# VALVEBOARD_ValvePower_ValveInterface.net
KiCad netlist of a schematic drawn in Altium Designer
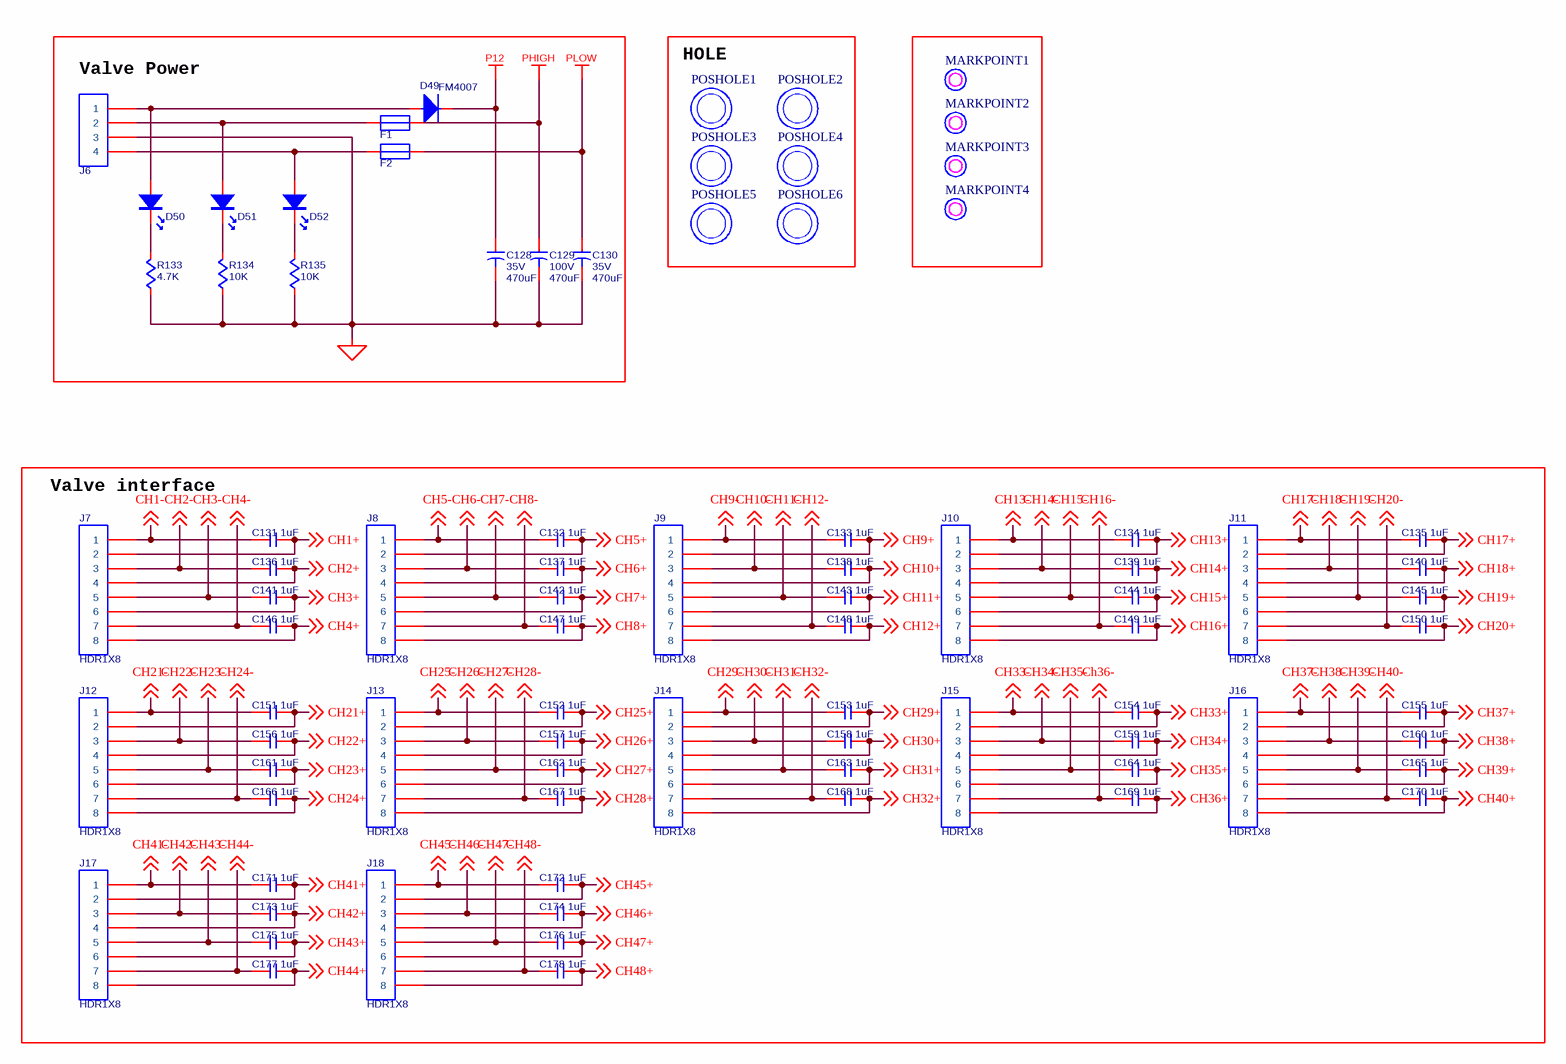
[diagram p0: VALVEBOARD_ValvePower_ValveInterface.SchDoc]

(export (version "E")
  (design (tool "Eeschema 10.0.6"))
  (components
    (comp (ref "C128")
      (value "470uF")
      (footprint "C_10_10R2")
      (fields (field (name "VOLTAGE") "35V") (field (name "Comment") "C-POL"))
      (libsource (lib "") (part "C-POL_1"))
    )
    (comp (ref "C129")
      (value "470uF")
      (footprint "C_18_21")
      (fields (field (name "VOLTAGE") "100V") (field (name "Comment") "C-POL"))
      (libsource (lib "zynq") (part "C-POL"))
    )
    (comp (ref "C130")
      (value "470uF")
      (footprint "C_10_10R2")
      (fields (field (name "VOLTAGE") "35V") (field (name "Comment") "C-POL"))
      (libsource (lib "") (part "C-POL_1"))
    )
    (comp (ref "C131")
      (value "1uF")
      (footprint "zynq:C0805")
      (fields (field (name "VOLTAGE") "25V") (field (name "Comment") "C-NOMO"))
      (libsource (lib "zynq") (part "C-NOMO"))
    )
    (comp (ref "C132")
      (value "1uF")
      (footprint "zynq:C0805")
      (fields (field (name "VOLTAGE") "25V") (field (name "Comment") "C-NOMO"))
      (libsource (lib "zynq") (part "C-NOMO"))
    )
    (comp (ref "C133")
      (value "1uF")
      (footprint "zynq:C0805")
      (fields (field (name "VOLTAGE") "25V") (field (name "Comment") "C-NOMO"))
      (libsource (lib "zynq") (part "C-NOMO"))
    )
    (comp (ref "C134")
      (value "1uF")
      (footprint "zynq:C0805")
      (fields (field (name "VOLTAGE") "25V") (field (name "Comment") "C-NOMO"))
      (libsource (lib "zynq") (part "C-NOMO"))
    )
    (comp (ref "C135")
      (value "1uF")
      (footprint "zynq:C0805")
      (fields (field (name "VOLTAGE") "25V") (field (name "Comment") "C-NOMO"))
      (libsource (lib "zynq") (part "C-NOMO"))
    )
    (comp (ref "C136")
      (value "1uF")
      (footprint "zynq:C0805")
      (fields (field (name "VOLTAGE") "25V") (field (name "Comment") "C-NOMO"))
      (libsource (lib "zynq") (part "C-NOMO"))
    )
    (comp (ref "C137")
      (value "1uF")
      (footprint "zynq:C0805")
      (fields (field (name "VOLTAGE") "25V") (field (name "Comment") "C-NOMO"))
      (libsource (lib "zynq") (part "C-NOMO"))
    )
    (comp (ref "C138")
      (value "1uF")
      (footprint "zynq:C0805")
      (fields (field (name "VOLTAGE") "25V") (field (name "Comment") "C-NOMO"))
      (libsource (lib "zynq") (part "C-NOMO"))
    )
    (comp (ref "C139")
      (value "1uF")
      (footprint "zynq:C0805")
      (fields (field (name "VOLTAGE") "25V") (field (name "Comment") "C-NOMO"))
      (libsource (lib "zynq") (part "C-NOMO"))
    )
    (comp (ref "C140")
      (value "1uF")
      (footprint "zynq:C0805")
      (fields (field (name "VOLTAGE") "25V") (field (name "Comment") "C-NOMO"))
      (libsource (lib "zynq") (part "C-NOMO"))
    )
    (comp (ref "C141")
      (value "1uF")
      (footprint "zynq:C0805")
      (fields (field (name "VOLTAGE") "25V") (field (name "Comment") "C-NOMO"))
      (libsource (lib "zynq") (part "C-NOMO"))
    )
    (comp (ref "C142")
      (value "1uF")
      (footprint "zynq:C0805")
      (fields (field (name "VOLTAGE") "25V") (field (name "Comment") "C-NOMO"))
      (libsource (lib "zynq") (part "C-NOMO"))
    )
    (comp (ref "C143")
      (value "1uF")
      (footprint "zynq:C0805")
      (fields (field (name "VOLTAGE") "25V") (field (name "Comment") "C-NOMO"))
      (libsource (lib "zynq") (part "C-NOMO"))
    )
    (comp (ref "C144")
      (value "1uF")
      (footprint "zynq:C0805")
      (fields (field (name "VOLTAGE") "25V") (field (name "Comment") "C-NOMO"))
      (libsource (lib "zynq") (part "C-NOMO"))
    )
    (comp (ref "C145")
      (value "1uF")
      (footprint "zynq:C0805")
      (fields (field (name "VOLTAGE") "25V") (field (name "Comment") "C-NOMO"))
      (libsource (lib "zynq") (part "C-NOMO"))
    )
    (comp (ref "C146")
      (value "1uF")
      (footprint "zynq:C0805")
      (fields (field (name "VOLTAGE") "25V") (field (name "Comment") "C-NOMO"))
      (libsource (lib "zynq") (part "C-NOMO"))
    )
    (comp (ref "C147")
      (value "1uF")
      (footprint "zynq:C0805")
      (fields (field (name "VOLTAGE") "25V") (field (name "Comment") "C-NOMO"))
      (libsource (lib "zynq") (part "C-NOMO"))
    )
    (comp (ref "C148")
      (value "1uF")
      (footprint "zynq:C0805")
      (fields (field (name "VOLTAGE") "25V") (field (name "Comment") "C-NOMO"))
      (libsource (lib "zynq") (part "C-NOMO"))
    )
    (comp (ref "C149")
      (value "1uF")
      (footprint "zynq:C0805")
      (fields (field (name "VOLTAGE") "25V") (field (name "Comment") "C-NOMO"))
      (libsource (lib "zynq") (part "C-NOMO"))
    )
    (comp (ref "C150")
      (value "1uF")
      (footprint "zynq:C0805")
      (fields (field (name "VOLTAGE") "25V") (field (name "Comment") "C-NOMO"))
      (libsource (lib "zynq") (part "C-NOMO"))
    )
    (comp (ref "C151")
      (value "1uF")
      (footprint "zynq:C0805")
      (fields (field (name "VOLTAGE") "25V") (field (name "Comment") "C-NOMO"))
      (libsource (lib "zynq") (part "C-NOMO"))
    )
    (comp (ref "C152")
      (value "1uF")
      (footprint "zynq:C0805")
      (fields (field (name "VOLTAGE") "25V") (field (name "Comment") "C-NOMO"))
      (libsource (lib "zynq") (part "C-NOMO"))
    )
    (comp (ref "C153")
      (value "1uF")
      (footprint "zynq:C0805")
      (fields (field (name "VOLTAGE") "25V") (field (name "Comment") "C-NOMO"))
      (libsource (lib "zynq") (part "C-NOMO"))
    )
    (comp (ref "C154")
      (value "1uF")
      (footprint "zynq:C0805")
      (fields (field (name "VOLTAGE") "25V") (field (name "Comment") "C-NOMO"))
      (libsource (lib "zynq") (part "C-NOMO"))
    )
    (comp (ref "C155")
      (value "1uF")
      (footprint "zynq:C0805")
      (fields (field (name "VOLTAGE") "25V") (field (name "Comment") "C-NOMO"))
      (libsource (lib "zynq") (part "C-NOMO"))
    )
    (comp (ref "C156")
      (value "1uF")
      (footprint "zynq:C0805")
      (fields (field (name "VOLTAGE") "25V") (field (name "Comment") "C-NOMO"))
      (libsource (lib "zynq") (part "C-NOMO"))
    )
    (comp (ref "C157")
      (value "1uF")
      (footprint "zynq:C0805")
      (fields (field (name "VOLTAGE") "25V") (field (name "Comment") "C-NOMO"))
      (libsource (lib "zynq") (part "C-NOMO"))
    )
    (comp (ref "C158")
      (value "1uF")
      (footprint "zynq:C0805")
      (fields (field (name "VOLTAGE") "25V") (field (name "Comment") "C-NOMO"))
      (libsource (lib "zynq") (part "C-NOMO"))
    )
    (comp (ref "C159")
      (value "1uF")
      (footprint "zynq:C0805")
      (fields (field (name "VOLTAGE") "25V") (field (name "Comment") "C-NOMO"))
      (libsource (lib "zynq") (part "C-NOMO"))
    )
    (comp (ref "C160")
      (value "1uF")
      (footprint "zynq:C0805")
      (fields (field (name "VOLTAGE") "25V") (field (name "Comment") "C-NOMO"))
      (libsource (lib "zynq") (part "C-NOMO"))
    )
    (comp (ref "C161")
      (value "1uF")
      (footprint "zynq:C0805")
      (fields (field (name "VOLTAGE") "25V") (field (name "Comment") "C-NOMO"))
      (libsource (lib "zynq") (part "C-NOMO"))
    )
    (comp (ref "C162")
      (value "1uF")
      (footprint "zynq:C0805")
      (fields (field (name "VOLTAGE") "25V") (field (name "Comment") "C-NOMO"))
      (libsource (lib "zynq") (part "C-NOMO"))
    )
    (comp (ref "C163")
      (value "1uF")
      (footprint "zynq:C0805")
      (fields (field (name "VOLTAGE") "25V") (field (name "Comment") "C-NOMO"))
      (libsource (lib "zynq") (part "C-NOMO"))
    )
    (comp (ref "C164")
      (value "1uF")
      (footprint "zynq:C0805")
      (fields (field (name "VOLTAGE") "25V") (field (name "Comment") "C-NOMO"))
      (libsource (lib "zynq") (part "C-NOMO"))
    )
    (comp (ref "C165")
      (value "1uF")
      (footprint "zynq:C0805")
      (fields (field (name "VOLTAGE") "25V") (field (name "Comment") "C-NOMO"))
      (libsource (lib "zynq") (part "C-NOMO"))
    )
    (comp (ref "C166")
      (value "1uF")
      (footprint "zynq:C0805")
      (fields (field (name "VOLTAGE") "25V") (field (name "Comment") "C-NOMO"))
      (libsource (lib "zynq") (part "C-NOMO"))
    )
    (comp (ref "C167")
      (value "1uF")
      (footprint "zynq:C0805")
      (fields (field (name "VOLTAGE") "25V") (field (name "Comment") "C-NOMO"))
      (libsource (lib "zynq") (part "C-NOMO"))
    )
    (comp (ref "C168")
      (value "1uF")
      (footprint "zynq:C0805")
      (fields (field (name "VOLTAGE") "25V") (field (name "Comment") "C-NOMO"))
      (libsource (lib "zynq") (part "C-NOMO"))
    )
    (comp (ref "C169")
      (value "1uF")
      (footprint "zynq:C0805")
      (fields (field (name "VOLTAGE") "25V") (field (name "Comment") "C-NOMO"))
      (libsource (lib "zynq") (part "C-NOMO"))
    )
    (comp (ref "C170")
      (value "1uF")
      (footprint "zynq:C0805")
      (fields (field (name "VOLTAGE") "25V") (field (name "Comment") "C-NOMO"))
      (libsource (lib "zynq") (part "C-NOMO"))
    )
    (comp (ref "C171")
      (value "1uF")
      (footprint "zynq:C0805")
      (fields (field (name "VOLTAGE") "25V") (field (name "Comment") "C-NOMO"))
      (libsource (lib "zynq") (part "C-NOMO"))
    )
    (comp (ref "C172")
      (value "1uF")
      (footprint "zynq:C0805")
      (fields (field (name "VOLTAGE") "25V") (field (name "Comment") "C-NOMO"))
      (libsource (lib "zynq") (part "C-NOMO"))
    )
    (comp (ref "C173")
      (value "1uF")
      (footprint "zynq:C0805")
      (fields (field (name "VOLTAGE") "25V") (field (name "Comment") "C-NOMO"))
      (libsource (lib "zynq") (part "C-NOMO"))
    )
    (comp (ref "C174")
      (value "1uF")
      (footprint "zynq:C0805")
      (fields (field (name "VOLTAGE") "25V") (field (name "Comment") "C-NOMO"))
      (libsource (lib "zynq") (part "C-NOMO"))
    )
    (comp (ref "C175")
      (value "1uF")
      (footprint "zynq:C0805")
      (fields (field (name "VOLTAGE") "25V") (field (name "Comment") "C-NOMO"))
      (libsource (lib "zynq") (part "C-NOMO"))
    )
    (comp (ref "C176")
      (value "1uF")
      (footprint "zynq:C0805")
      (fields (field (name "VOLTAGE") "25V") (field (name "Comment") "C-NOMO"))
      (libsource (lib "zynq") (part "C-NOMO"))
    )
    (comp (ref "C177")
      (value "1uF")
      (footprint "zynq:C0805")
      (fields (field (name "VOLTAGE") "25V") (field (name "Comment") "C-NOMO"))
      (libsource (lib "zynq") (part "C-NOMO"))
    )
    (comp (ref "C178")
      (value "1uF")
      (footprint "zynq:C0805")
      (fields (field (name "VOLTAGE") "25V") (field (name "Comment") "C-NOMO"))
      (libsource (lib "zynq") (part "C-NOMO"))
    )
    (comp (ref "D49")
      (value "FM4007")
      (footprint "zynq:FM4007-T(A7)")
      (libsource (lib "zynq") (part "FM4007"))
    )
    (comp (ref "D50") (value "LED") (footprint "zynq:LED0603") (libsource (lib "zynq") (part "LED")))
    (comp (ref "D51") (value "LED") (footprint "zynq:LED0603") (libsource (lib "zynq") (part "LED")))
    (comp (ref "D52") (value "LED") (footprint "zynq:LED0603") (libsource (lib "zynq") (part "LED")))
    (comp (ref "F1") (value "F50") (footprint "zynq:F-TH2") (libsource (lib "zynq") (part "F50")))
    (comp (ref "F2") (value "F50") (footprint "zynq:F-TH2") (libsource (lib "zynq") (part "F50")))
    (comp (ref "J6")
      (value "HDR1X4")
      (footprint "zynq:KF301-5.0-4P")
      (libsource (lib "zynq") (part "HDR1X4"))
    )
    (comp (ref "J7") (value "HDR1X8") (footprint "KF15EDGK-3.81-8P") (libsource (lib "zynq") (part "HDR1X8")))
    (comp (ref "J8") (value "HDR1X8") (footprint "KF15EDGK-3.81-8P") (libsource (lib "zynq") (part "HDR1X8")))
    (comp (ref "J9") (value "HDR1X8") (footprint "KF15EDGK-3.81-8P") (libsource (lib "zynq") (part "HDR1X8")))
    (comp (ref "J10")
      (value "HDR1X8")
      (footprint "KF15EDGK-3.81-8P")
      (libsource (lib "zynq") (part "HDR1X8"))
    )
    (comp (ref "J11")
      (value "HDR1X8")
      (footprint "KF15EDGK-3.81-8P")
      (libsource (lib "zynq") (part "HDR1X8"))
    )
    (comp (ref "J12")
      (value "HDR1X8")
      (footprint "KF15EDGK-3.81-8P")
      (libsource (lib "zynq") (part "HDR1X8"))
    )
    (comp (ref "J13")
      (value "HDR1X8")
      (footprint "KF15EDGK-3.81-8P")
      (libsource (lib "zynq") (part "HDR1X8"))
    )
    (comp (ref "J14")
      (value "HDR1X8")
      (footprint "KF15EDGK-3.81-8P")
      (libsource (lib "zynq") (part "HDR1X8"))
    )
    (comp (ref "J15")
      (value "HDR1X8")
      (footprint "KF15EDGK-3.81-8P")
      (libsource (lib "zynq") (part "HDR1X8"))
    )
    (comp (ref "J16")
      (value "HDR1X8")
      (footprint "KF15EDGK-3.81-8P")
      (libsource (lib "zynq") (part "HDR1X8"))
    )
    (comp (ref "J17")
      (value "HDR1X8")
      (footprint "KF15EDGK-3.81-8P")
      (libsource (lib "zynq") (part "HDR1X8"))
    )
    (comp (ref "J18")
      (value "HDR1X8")
      (footprint "KF15EDGK-3.81-8P")
      (libsource (lib "zynq") (part "HDR1X8"))
    )
    (comp (ref "MARKPOINT1")
      (value "MARKPOINT")
      (footprint "zynq:MARKPOINT-1.0")
      (libsource (lib "zynq") (part "MARKPOINT"))
    )
    (comp (ref "MARKPOINT2")
      (value "MARKPOINT")
      (footprint "zynq:MARKPOINT-1.0")
      (libsource (lib "zynq") (part "MARKPOINT"))
    )
    (comp (ref "MARKPOINT3")
      (value "MARKPOINT")
      (footprint "zynq:MARKPOINT-1.0")
      (libsource (lib "zynq") (part "MARKPOINT"))
    )
    (comp (ref "MARKPOINT4")
      (value "MARKPOINT")
      (footprint "zynq:MARKPOINT-1.0")
      (libsource (lib "zynq") (part "MARKPOINT"))
    )
    (comp (ref "POSHOLE1")
      (value "POSHOLE")
      (footprint "zynq:POSHOLE-3.2")
      (libsource (lib "zynq") (part "POSHOLE"))
    )
    (comp (ref "POSHOLE2")
      (value "POSHOLE")
      (footprint "zynq:POSHOLE-3.2")
      (libsource (lib "zynq") (part "POSHOLE"))
    )
    (comp (ref "POSHOLE3")
      (value "POSHOLE")
      (footprint "zynq:POSHOLE-3.2")
      (libsource (lib "zynq") (part "POSHOLE"))
    )
    (comp (ref "POSHOLE4")
      (value "POSHOLE")
      (footprint "zynq:POSHOLE-3.2")
      (libsource (lib "zynq") (part "POSHOLE"))
    )
    (comp (ref "POSHOLE5")
      (value "POSHOLE")
      (footprint "zynq:POSHOLE-3.2")
      (libsource (lib "zynq") (part "POSHOLE"))
    )
    (comp (ref "POSHOLE6")
      (value "POSHOLE")
      (footprint "zynq:POSHOLE-3.2")
      (libsource (lib "zynq") (part "POSHOLE"))
    )
    (comp (ref "R133")
      (value "4.7K")
      (footprint "zynq:R0402")
      (fields (field (name "Comment") "R"))
      (libsource (lib "zynq") (part "R"))
    )
    (comp (ref "R134")
      (value "10K")
      (footprint "zynq:R0402")
      (fields (field (name "Comment") "R"))
      (libsource (lib "zynq") (part "R"))
    )
    (comp (ref "R135")
      (value "10K")
      (footprint "zynq:R0402")
      (fields (field (name "Comment") "R"))
      (libsource (lib "zynq") (part "R"))
    )
  )
  (nets
    (net (code "2") (name "CH1+") (class "Default")
      (node (ref "C131") (pin "1") (pinfunction "1_1") (pintype "passive"))
      (node (ref "J7") (pin "2") (pinfunction "2_2") (pintype "passive"))
    )
    (net (code "3") (name "CH1-") (class "Default")
      (node (ref "C131") (pin "2") (pinfunction "2_2") (pintype "passive"))
      (node (ref "J7") (pin "1") (pinfunction "1_1") (pintype "passive"))
    )
    (net (code "4") (name "CH2+") (class "Default")
      (node (ref "C136") (pin "1") (pinfunction "1_1") (pintype "passive"))
      (node (ref "J7") (pin "4") (pinfunction "4_4") (pintype "passive"))
    )
    (net (code "5") (name "CH2-") (class "Default")
      (node (ref "C136") (pin "2") (pinfunction "2_2") (pintype "passive"))
      (node (ref "J7") (pin "3") (pinfunction "3_3") (pintype "passive"))
    )
    (net (code "6") (name "CH3+") (class "Default")
      (node (ref "C141") (pin "1") (pinfunction "1_1") (pintype "passive"))
      (node (ref "J7") (pin "6") (pinfunction "6_6") (pintype "passive"))
    )
    (net (code "7") (name "CH3-") (class "Default")
      (node (ref "C141") (pin "2") (pinfunction "2_2") (pintype "passive"))
      (node (ref "J7") (pin "5") (pinfunction "5_5") (pintype "passive"))
    )
    (net (code "8") (name "CH4+") (class "Default")
      (node (ref "C146") (pin "1") (pinfunction "1_1") (pintype "passive"))
      (node (ref "J7") (pin "8") (pinfunction "8_8") (pintype "passive"))
    )
    (net (code "9") (name "CH4-") (class "Default")
      (node (ref "C146") (pin "2") (pinfunction "2_2") (pintype "passive"))
      (node (ref "J7") (pin "7") (pinfunction "7_7") (pintype "passive"))
    )
    (net (code "10") (name "CH5+") (class "Default")
      (node (ref "C132") (pin "1") (pinfunction "1_1") (pintype "passive"))
      (node (ref "J8") (pin "2") (pinfunction "2_2") (pintype "passive"))
    )
    (net (code "11") (name "CH5-") (class "Default")
      (node (ref "C132") (pin "2") (pinfunction "2_2") (pintype "passive"))
      (node (ref "J8") (pin "1") (pinfunction "1_1") (pintype "passive"))
    )
    (net (code "12") (name "CH6+") (class "Default")
      (node (ref "C137") (pin "1") (pinfunction "1_1") (pintype "passive"))
      (node (ref "J8") (pin "4") (pinfunction "4_4") (pintype "passive"))
    )
    (net (code "13") (name "CH6-") (class "Default")
      (node (ref "C137") (pin "2") (pinfunction "2_2") (pintype "passive"))
      (node (ref "J8") (pin "3") (pinfunction "3_3") (pintype "passive"))
    )
    (net (code "14") (name "CH7+") (class "Default")
      (node (ref "C142") (pin "1") (pinfunction "1_1") (pintype "passive"))
      (node (ref "J8") (pin "6") (pinfunction "6_6") (pintype "passive"))
    )
    (net (code "15") (name "CH7-") (class "Default")
      (node (ref "C142") (pin "2") (pinfunction "2_2") (pintype "passive"))
      (node (ref "J8") (pin "5") (pinfunction "5_5") (pintype "passive"))
    )
    (net (code "16") (name "CH8+") (class "Default")
      (node (ref "C147") (pin "1") (pinfunction "1_1") (pintype "passive"))
      (node (ref "J8") (pin "8") (pinfunction "8_8") (pintype "passive"))
    )
    (net (code "17") (name "CH8-") (class "Default")
      (node (ref "C147") (pin "2") (pinfunction "2_2") (pintype "passive"))
      (node (ref "J8") (pin "7") (pinfunction "7_7") (pintype "passive"))
    )
    (net (code "18") (name "CH9+") (class "Default")
      (node (ref "C133") (pin "1") (pinfunction "1_1") (pintype "passive"))
      (node (ref "J9") (pin "2") (pinfunction "2_2") (pintype "passive"))
    )
    (net (code "19") (name "CH9-") (class "Default")
      (node (ref "C133") (pin "2") (pinfunction "2_2") (pintype "passive"))
      (node (ref "J9") (pin "1") (pinfunction "1_1") (pintype "passive"))
    )
    (net (code "20") (name "CH10+") (class "Default")
      (node (ref "C138") (pin "1") (pinfunction "1_1") (pintype "passive"))
      (node (ref "J9") (pin "4") (pinfunction "4_4") (pintype "passive"))
    )
    (net (code "21") (name "CH10-") (class "Default")
      (node (ref "C138") (pin "2") (pinfunction "2_2") (pintype "passive"))
      (node (ref "J9") (pin "3") (pinfunction "3_3") (pintype "passive"))
    )
    (net (code "22") (name "CH11+") (class "Default")
      (node (ref "C143") (pin "1") (pinfunction "1_1") (pintype "passive"))
      (node (ref "J9") (pin "6") (pinfunction "6_6") (pintype "passive"))
    )
    (net (code "23") (name "CH11-") (class "Default")
      (node (ref "C143") (pin "2") (pinfunction "2_2") (pintype "passive"))
      (node (ref "J9") (pin "5") (pinfunction "5_5") (pintype "passive"))
    )
    (net (code "24") (name "CH12+") (class "Default")
      (node (ref "C148") (pin "1") (pinfunction "1_1") (pintype "passive"))
      (node (ref "J9") (pin "8") (pinfunction "8_8") (pintype "passive"))
    )
    (net (code "25") (name "CH12-") (class "Default")
      (node (ref "C148") (pin "2") (pinfunction "2_2") (pintype "passive"))
      (node (ref "J9") (pin "7") (pinfunction "7_7") (pintype "passive"))
    )
    (net (code "26") (name "CH13+") (class "Default")
      (node (ref "C134") (pin "1") (pinfunction "1_1") (pintype "passive"))
      (node (ref "J10") (pin "2") (pinfunction "2_2") (pintype "passive"))
    )
    (net (code "27") (name "CH13-") (class "Default")
      (node (ref "C134") (pin "2") (pinfunction "2_2") (pintype "passive"))
      (node (ref "J10") (pin "1") (pinfunction "1_1") (pintype "passive"))
    )
    (net (code "28") (name "CH14+") (class "Default")
      (node (ref "C139") (pin "1") (pinfunction "1_1") (pintype "passive"))
      (node (ref "J10") (pin "4") (pinfunction "4_4") (pintype "passive"))
    )
    (net (code "29") (name "CH14-") (class "Default")
      (node (ref "C139") (pin "2") (pinfunction "2_2") (pintype "passive"))
      (node (ref "J10") (pin "3") (pinfunction "3_3") (pintype "passive"))
    )
    (net (code "30") (name "CH15+") (class "Default")
      (node (ref "C144") (pin "1") (pinfunction "1_1") (pintype "passive"))
      (node (ref "J10") (pin "6") (pinfunction "6_6") (pintype "passive"))
    )
    (net (code "31") (name "CH15-") (class "Default")
      (node (ref "C144") (pin "2") (pinfunction "2_2") (pintype "passive"))
      (node (ref "J10") (pin "5") (pinfunction "5_5") (pintype "passive"))
    )
    (net (code "32") (name "CH16+") (class "Default")
      (node (ref "C149") (pin "1") (pinfunction "1_1") (pintype "passive"))
      (node (ref "J10") (pin "8") (pinfunction "8_8") (pintype "passive"))
    )
    (net (code "33") (name "CH16-") (class "Default")
      (node (ref "C149") (pin "2") (pinfunction "2_2") (pintype "passive"))
      (node (ref "J10") (pin "7") (pinfunction "7_7") (pintype "passive"))
    )
    (net (code "34") (name "CH17+") (class "Default")
      (node (ref "C135") (pin "1") (pinfunction "1_1") (pintype "passive"))
      (node (ref "J11") (pin "2") (pinfunction "2_2") (pintype "passive"))
    )
    (net (code "35") (name "CH17-") (class "Default")
      (node (ref "C135") (pin "2") (pinfunction "2_2") (pintype "passive"))
      (node (ref "J11") (pin "1") (pinfunction "1_1") (pintype "passive"))
    )
    (net (code "36") (name "CH18+") (class "Default")
      (node (ref "C140") (pin "1") (pinfunction "1_1") (pintype "passive"))
      (node (ref "J11") (pin "4") (pinfunction "4_4") (pintype "passive"))
    )
    (net (code "37") (name "CH18-") (class "Default")
      (node (ref "C140") (pin "2") (pinfunction "2_2") (pintype "passive"))
      (node (ref "J11") (pin "3") (pinfunction "3_3") (pintype "passive"))
    )
    (net (code "38") (name "CH19+") (class "Default")
      (node (ref "C145") (pin "1") (pinfunction "1_1") (pintype "passive"))
      (node (ref "J11") (pin "6") (pinfunction "6_6") (pintype "passive"))
    )
    (net (code "39") (name "CH19-") (class "Default")
      (node (ref "C145") (pin "2") (pinfunction "2_2") (pintype "passive"))
      (node (ref "J11") (pin "5") (pinfunction "5_5") (pintype "passive"))
    )
    (net (code "40") (name "CH20+") (class "Default")
      (node (ref "C150") (pin "1") (pinfunction "1_1") (pintype "passive"))
      (node (ref "J11") (pin "8") (pinfunction "8_8") (pintype "passive"))
    )
    (net (code "41") (name "CH20-") (class "Default")
      (node (ref "C150") (pin "2") (pinfunction "2_2") (pintype "passive"))
      (node (ref "J11") (pin "7") (pinfunction "7_7") (pintype "passive"))
    )
    (net (code "42") (name "CH21+") (class "Default")
      (node (ref "C151") (pin "1") (pinfunction "1_1") (pintype "passive"))
      (node (ref "J12") (pin "2") (pinfunction "2_2") (pintype "passive"))
    )
    (net (code "43") (name "CH21-") (class "Default")
      (node (ref "C151") (pin "2") (pinfunction "2_2") (pintype "passive"))
      (node (ref "J12") (pin "1") (pinfunction "1_1") (pintype "passive"))
    )
    (net (code "44") (name "CH22+") (class "Default")
      (node (ref "C156") (pin "1") (pinfunction "1_1") (pintype "passive"))
      (node (ref "J12") (pin "4") (pinfunction "4_4") (pintype "passive"))
    )
    (net (code "45") (name "CH22-") (class "Default")
      (node (ref "C156") (pin "2") (pinfunction "2_2") (pintype "passive"))
      (node (ref "J12") (pin "3") (pinfunction "3_3") (pintype "passive"))
    )
    (net (code "46") (name "CH23+") (class "Default")
      (node (ref "C161") (pin "1") (pinfunction "1_1") (pintype "passive"))
      (node (ref "J12") (pin "6") (pinfunction "6_6") (pintype "passive"))
    )
    (net (code "47") (name "CH23-") (class "Default")
      (node (ref "C161") (pin "2") (pinfunction "2_2") (pintype "passive"))
      (node (ref "J12") (pin "5") (pinfunction "5_5") (pintype "passive"))
    )
    (net (code "48") (name "CH24+") (class "Default")
      (node (ref "C166") (pin "1") (pinfunction "1_1") (pintype "passive"))
      (node (ref "J12") (pin "8") (pinfunction "8_8") (pintype "passive"))
    )
    (net (code "49") (name "CH24-") (class "Default")
      (node (ref "C166") (pin "2") (pinfunction "2_2") (pintype "passive"))
      (node (ref "J12") (pin "7") (pinfunction "7_7") (pintype "passive"))
    )
    (net (code "50") (name "CH25+") (class "Default")
      (node (ref "C152") (pin "1") (pinfunction "1_1") (pintype "passive"))
      (node (ref "J13") (pin "2") (pinfunction "2_2") (pintype "passive"))
    )
    (net (code "51") (name "CH25-") (class "Default")
      (node (ref "C152") (pin "2") (pinfunction "2_2") (pintype "passive"))
      (node (ref "J13") (pin "1") (pinfunction "1_1") (pintype "passive"))
    )
    (net (code "52") (name "CH26+") (class "Default")
      (node (ref "C157") (pin "1") (pinfunction "1_1") (pintype "passive"))
      (node (ref "J13") (pin "4") (pinfunction "4_4") (pintype "passive"))
    )
    (net (code "53") (name "CH26-") (class "Default")
      (node (ref "C157") (pin "2") (pinfunction "2_2") (pintype "passive"))
      (node (ref "J13") (pin "3") (pinfunction "3_3") (pintype "passive"))
    )
    (net (code "54") (name "CH27+") (class "Default")
      (node (ref "C162") (pin "1") (pinfunction "1_1") (pintype "passive"))
      (node (ref "J13") (pin "6") (pinfunction "6_6") (pintype "passive"))
    )
    (net (code "55") (name "CH27-") (class "Default")
      (node (ref "C162") (pin "2") (pinfunction "2_2") (pintype "passive"))
      (node (ref "J13") (pin "5") (pinfunction "5_5") (pintype "passive"))
    )
    (net (code "56") (name "CH28+") (class "Default")
      (node (ref "C167") (pin "1") (pinfunction "1_1") (pintype "passive"))
      (node (ref "J13") (pin "8") (pinfunction "8_8") (pintype "passive"))
    )
    (net (code "57") (name "CH28-") (class "Default")
      (node (ref "C167") (pin "2") (pinfunction "2_2") (pintype "passive"))
      (node (ref "J13") (pin "7") (pinfunction "7_7") (pintype "passive"))
    )
    (net (code "58") (name "CH29+") (class "Default")
      (node (ref "C153") (pin "1") (pinfunction "1_1") (pintype "passive"))
      (node (ref "J14") (pin "2") (pinfunction "2_2") (pintype "passive"))
    )
    (net (code "59") (name "CH29-") (class "Default")
      (node (ref "C153") (pin "2") (pinfunction "2_2") (pintype "passive"))
      (node (ref "J14") (pin "1") (pinfunction "1_1") (pintype "passive"))
    )
    (net (code "60") (name "CH30+") (class "Default")
      (node (ref "C158") (pin "1") (pinfunction "1_1") (pintype "passive"))
      (node (ref "J14") (pin "4") (pinfunction "4_4") (pintype "passive"))
    )
    (net (code "61") (name "CH30-") (class "Default")
      (node (ref "C158") (pin "2") (pinfunction "2_2") (pintype "passive"))
      (node (ref "J14") (pin "3") (pinfunction "3_3") (pintype "passive"))
    )
    (net (code "62") (name "CH31+") (class "Default")
      (node (ref "C163") (pin "1") (pinfunction "1_1") (pintype "passive"))
      (node (ref "J14") (pin "6") (pinfunction "6_6") (pintype "passive"))
    )
    (net (code "63") (name "CH31-") (class "Default")
      (node (ref "C163") (pin "2") (pinfunction "2_2") (pintype "passive"))
      (node (ref "J14") (pin "5") (pinfunction "5_5") (pintype "passive"))
    )
    (net (code "64") (name "CH32+") (class "Default")
      (node (ref "C168") (pin "1") (pinfunction "1_1") (pintype "passive"))
      (node (ref "J14") (pin "8") (pinfunction "8_8") (pintype "passive"))
    )
    (net (code "65") (name "CH32-") (class "Default")
      (node (ref "C168") (pin "2") (pinfunction "2_2") (pintype "passive"))
      (node (ref "J14") (pin "7") (pinfunction "7_7") (pintype "passive"))
    )
    (net (code "66") (name "CH33+") (class "Default")
      (node (ref "C154") (pin "1") (pinfunction "1_1") (pintype "passive"))
      (node (ref "J15") (pin "2") (pinfunction "2_2") (pintype "passive"))
    )
    (net (code "67") (name "CH33-") (class "Default")
      (node (ref "C154") (pin "2") (pinfunction "2_2") (pintype "passive"))
      (node (ref "J15") (pin "1") (pinfunction "1_1") (pintype "passive"))
    )
    (net (code "68") (name "CH34+") (class "Default")
      (node (ref "C159") (pin "1") (pinfunction "1_1") (pintype "passive"))
      (node (ref "J15") (pin "4") (pinfunction "4_4") (pintype "passive"))
    )
    (net (code "69") (name "CH34-") (class "Default")
      (node (ref "C159") (pin "2") (pinfunction "2_2") (pintype "passive"))
      (node (ref "J15") (pin "3") (pinfunction "3_3") (pintype "passive"))
    )
    (net (code "70") (name "CH35+") (class "Default")
      (node (ref "C164") (pin "1") (pinfunction "1_1") (pintype "passive"))
      (node (ref "J15") (pin "6") (pinfunction "6_6") (pintype "passive"))
    )
    (net (code "71") (name "CH35-") (class "Default")
      (node (ref "C164") (pin "2") (pinfunction "2_2") (pintype "passive"))
      (node (ref "J15") (pin "5") (pinfunction "5_5") (pintype "passive"))
    )
    (net (code "72") (name "CH36+") (class "Default")
      (node (ref "C169") (pin "1") (pinfunction "1_1") (pintype "passive"))
      (node (ref "J15") (pin "8") (pinfunction "8_8") (pintype "passive"))
    )
    (net (code "73") (name "CH37+") (class "Default")
      (node (ref "C155") (pin "1") (pinfunction "1_1") (pintype "passive"))
      (node (ref "J16") (pin "2") (pinfunction "2_2") (pintype "passive"))
    )
    (net (code "74") (name "CH37-") (class "Default")
      (node (ref "C155") (pin "2") (pinfunction "2_2") (pintype "passive"))
      (node (ref "J16") (pin "1") (pinfunction "1_1") (pintype "passive"))
    )
    (net (code "75") (name "CH38+") (class "Default")
      (node (ref "C160") (pin "1") (pinfunction "1_1") (pintype "passive"))
      (node (ref "J16") (pin "4") (pinfunction "4_4") (pintype "passive"))
    )
    (net (code "76") (name "CH38-") (class "Default")
      (node (ref "C160") (pin "2") (pinfunction "2_2") (pintype "passive"))
      (node (ref "J16") (pin "3") (pinfunction "3_3") (pintype "passive"))
    )
    (net (code "77") (name "CH39+") (class "Default")
      (node (ref "C165") (pin "1") (pinfunction "1_1") (pintype "passive"))
      (node (ref "J16") (pin "6") (pinfunction "6_6") (pintype "passive"))
    )
    (net (code "78") (name "CH39-") (class "Default")
      (node (ref "C165") (pin "2") (pinfunction "2_2") (pintype "passive"))
      (node (ref "J16") (pin "5") (pinfunction "5_5") (pintype "passive"))
    )
    (net (code "79") (name "CH40+") (class "Default")
      (node (ref "C170") (pin "1") (pinfunction "1_1") (pintype "passive"))
      (node (ref "J16") (pin "8") (pinfunction "8_8") (pintype "passive"))
    )
    (net (code "80") (name "CH40-") (class "Default")
      (node (ref "C170") (pin "2") (pinfunction "2_2") (pintype "passive"))
      (node (ref "J16") (pin "7") (pinfunction "7_7") (pintype "passive"))
    )
    (net (code "81") (name "CH41+") (class "Default")
      (node (ref "C171") (pin "1") (pinfunction "1_1") (pintype "passive"))
      (node (ref "J17") (pin "2") (pinfunction "2_2") (pintype "passive"))
    )
    (net (code "82") (name "CH41-") (class "Default")
      (node (ref "C171") (pin "2") (pinfunction "2_2") (pintype "passive"))
      (node (ref "J17") (pin "1") (pinfunction "1_1") (pintype "passive"))
    )
    (net (code "83") (name "CH42+") (class "Default")
      (node (ref "C173") (pin "1") (pinfunction "1_1") (pintype "passive"))
      (node (ref "J17") (pin "4") (pinfunction "4_4") (pintype "passive"))
    )
    (net (code "84") (name "CH42-") (class "Default")
      (node (ref "C173") (pin "2") (pinfunction "2_2") (pintype "passive"))
      (node (ref "J17") (pin "3") (pinfunction "3_3") (pintype "passive"))
    )
    (net (code "85") (name "CH43+") (class "Default")
      (node (ref "C175") (pin "1") (pinfunction "1_1") (pintype "passive"))
      (node (ref "J17") (pin "6") (pinfunction "6_6") (pintype "passive"))
    )
    (net (code "86") (name "CH43-") (class "Default")
      (node (ref "C175") (pin "2") (pinfunction "2_2") (pintype "passive"))
      (node (ref "J17") (pin "5") (pinfunction "5_5") (pintype "passive"))
    )
    (net (code "87") (name "CH44+") (class "Default")
      (node (ref "C177") (pin "1") (pinfunction "1_1") (pintype "passive"))
      (node (ref "J17") (pin "8") (pinfunction "8_8") (pintype "passive"))
    )
    (net (code "88") (name "CH44-") (class "Default")
      (node (ref "C177") (pin "2") (pinfunction "2_2") (pintype "passive"))
      (node (ref "J17") (pin "7") (pinfunction "7_7") (pintype "passive"))
    )
    (net (code "89") (name "CH45+") (class "Default")
      (node (ref "C172") (pin "1") (pinfunction "1_1") (pintype "passive"))
      (node (ref "J18") (pin "2") (pinfunction "2_2") (pintype "passive"))
    )
    (net (code "90") (name "CH45-") (class "Default")
      (node (ref "C172") (pin "2") (pinfunction "2_2") (pintype "passive"))
      (node (ref "J18") (pin "1") (pinfunction "1_1") (pintype "passive"))
    )
    (net (code "91") (name "CH46+") (class "Default")
      (node (ref "C174") (pin "1") (pinfunction "1_1") (pintype "passive"))
      (node (ref "J18") (pin "4") (pinfunction "4_4") (pintype "passive"))
    )
    (net (code "92") (name "CH46-") (class "Default")
      (node (ref "C174") (pin "2") (pinfunction "2_2") (pintype "passive"))
      (node (ref "J18") (pin "3") (pinfunction "3_3") (pintype "passive"))
    )
    (net (code "93") (name "CH47+") (class "Default")
      (node (ref "C176") (pin "1") (pinfunction "1_1") (pintype "passive"))
      (node (ref "J18") (pin "6") (pinfunction "6_6") (pintype "passive"))
    )
    (net (code "94") (name "CH47-") (class "Default")
      (node (ref "C176") (pin "2") (pinfunction "2_2") (pintype "passive"))
      (node (ref "J18") (pin "5") (pinfunction "5_5") (pintype "passive"))
    )
    (net (code "95") (name "CH48+") (class "Default")
      (node (ref "C178") (pin "1") (pinfunction "1_1") (pintype "passive"))
      (node (ref "J18") (pin "8") (pinfunction "8_8") (pintype "passive"))
    )
    (net (code "96") (name "CH48-") (class "Default")
      (node (ref "C178") (pin "2") (pinfunction "2_2") (pintype "passive"))
      (node (ref "J18") (pin "7") (pinfunction "7_7") (pintype "passive"))
    )
    (net (code "97") (name "Ch36-") (class "Default")
      (node (ref "C169") (pin "2") (pinfunction "2_2") (pintype "passive"))
      (node (ref "J15") (pin "7") (pinfunction "7_7") (pintype "passive"))
    )
    (net (code "98") (name "Net-(D49-Pad2)") (class "Default")
      (node (ref "D49") (pin "2") (pinfunction "2_2") (pintype "passive"))
      (node (ref "D50") (pin "2") (pinfunction "2_2") (pintype "passive"))
      (node (ref "J6") (pin "1") (pinfunction "1_1") (pintype "passive"))
    )
    (net (code "99") (name "Net-(D50-Pad1)") (class "Default")
      (node (ref "D50") (pin "1") (pinfunction "1_1") (pintype "passive"))
      (node (ref "R133") (pin "1") (pinfunction "1_1") (pintype "passive"))
    )
    (net (code "100") (name "Net-(D51-Pad1)") (class "Default")
      (node (ref "D51") (pin "1") (pinfunction "1_1") (pintype "passive"))
      (node (ref "R134") (pin "1") (pinfunction "1_1") (pintype "passive"))
    )
    (net (code "101") (name "Net-(D51-Pad2)") (class "Default")
      (node (ref "D51") (pin "2") (pinfunction "2_2") (pintype "passive"))
      (node (ref "F1") (pin "1") (pintype "passive"))
      (node (ref "J6") (pin "2") (pinfunction "2_2") (pintype "passive"))
    )
    (net (code "102") (name "Net-(D52-Pad1)") (class "Default")
      (node (ref "D52") (pin "1") (pinfunction "1_1") (pintype "passive"))
      (node (ref "R135") (pin "1") (pinfunction "1_1") (pintype "passive"))
    )
    (net (code "103") (name "Net-(D52-Pad2)") (class "Default")
      (node (ref "D52") (pin "2") (pinfunction "2_2") (pintype "passive"))
      (node (ref "F2") (pin "1") (pintype "passive"))
      (node (ref "J6") (pin "4") (pinfunction "4_4") (pintype "passive"))
    )
    (net (code "104") (name "P12") (class "Default")
      (node (ref "C128") (pin "1") (pinfunction "S_1") (pintype "passive"))
      (node (ref "D49") (pin "1") (pinfunction "1_1") (pintype "passive"))
    )
    (net (code "105") (name "PGND") (class "Default")
      (node (ref "C128") (pin "2") (pinfunction "2_2") (pintype "passive"))
      (node (ref "C129") (pin "2") (pinfunction "2_2") (pintype "passive"))
      (node (ref "C130") (pin "2") (pinfunction "2_2") (pintype "passive"))
      (node (ref "J6") (pin "3") (pinfunction "3_3") (pintype "passive"))
      (node (ref "R133") (pin "2") (pinfunction "2_2") (pintype "passive"))
      (node (ref "R134") (pin "2") (pinfunction "2_2") (pintype "passive"))
      (node (ref "R135") (pin "2") (pinfunction "2_2") (pintype "passive"))
    )
    (net (code "106") (name "PHIGH") (class "Default")
      (node (ref "C129") (pin "1") (pinfunction "1_1") (pintype "passive"))
      (node (ref "F1") (pin "2") (pintype "passive"))
    )
    (net (code "107") (name "PLOW") (class "Default")
      (node (ref "C130") (pin "1") (pinfunction "S_1") (pintype "passive"))
      (node (ref "F2") (pin "2") (pintype "passive"))
    )
  )
)
